# FPGA_Bypass_3V3.net
KiCad netlist of a schematic drawn in Altium Designer
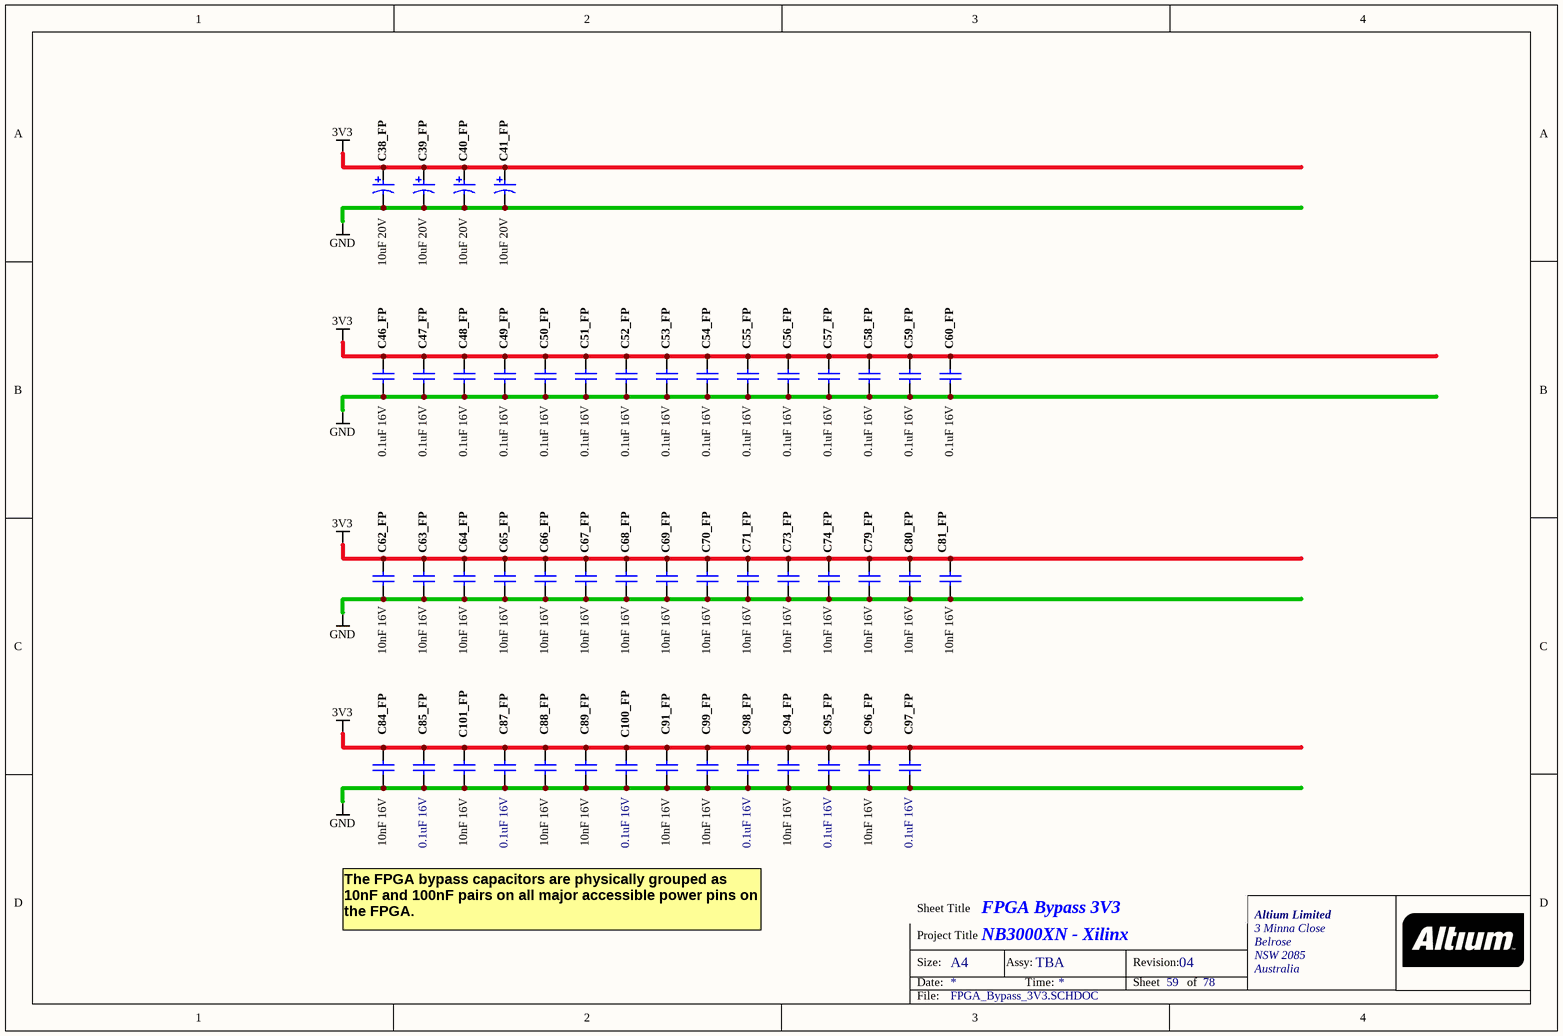
[diagram p0: FPGA_Bypass_3V3.SCHDOC]

(export (version "E")
  (design (tool "Eeschema 10.0.6"))
  (components
    (comp (ref "C38_FP")
      (value "10uF 20V")
      (footprint "CAPC3528-STAR")
      (description "Capacitor, Tantalum, 10uF 10% 20V MCCT-B (3528)")
      (fields (field (name "TOLERANCE") "10 %"))
      (libsource (lib "altium-import") (part "root_0_CAP-P_"))
    )
    (comp (ref "C39_FP")
      (value "10uF 20V")
      (footprint "CAPC3528-STAR")
      (description "Capacitor, Tantalum, 10uF 10% 20V MCCT-B (3528)")
      (fields (field (name "TOLERANCE") "10 %"))
      (libsource (lib "altium-import") (part "root_0_CAP-P_"))
    )
    (comp (ref "C40_FP")
      (value "10uF 20V")
      (footprint "CAPC3528-STAR")
      (description "Capacitor, Tantalum, 10uF 10% 20V MCCT-B (3528)")
      (fields (field (name "TOLERANCE") "10 %"))
      (libsource (lib "altium-import") (part "root_0_CAP-P_"))
    )
    (comp (ref "C41_FP")
      (value "10uF 20V")
      (footprint "CAPC3528-STAR")
      (description "Capacitor, Tantalum, 10uF 10% 20V MCCT-B (3528)")
      (fields (field (name "TOLERANCE") "10 %"))
      (libsource (lib "altium-import") (part "root_0_CAP-P_"))
    )
    (comp (ref "C46_FP")
      (value "0.1uF 16V")
      (footprint "CAPC1005-STAR")
      (description "Capacitor, Ceramic, 0.1uF 10% 16V 0402 (1005) X7R")
      (fields (field (name "TOLERANCE") "10 %"))
      (libsource (lib "altium-import") (part "root_0_mirrored_CAP-NP_"))
    )
    (comp (ref "C47_FP")
      (value "0.1uF 16V")
      (footprint "CAPC1005-STAR")
      (description "Capacitor, Ceramic, 0.1uF 10% 16V 0402 (1005) X7R")
      (fields (field (name "TOLERANCE") "10 %"))
      (libsource (lib "altium-import") (part "root_0_mirrored_CAP-NP_"))
    )
    (comp (ref "C48_FP")
      (value "0.1uF 16V")
      (footprint "CAPC1005-STAR")
      (description "Capacitor, Ceramic, 0.1uF 10% 16V 0402 (1005) X7R")
      (fields (field (name "TOLERANCE") "10 %"))
      (libsource (lib "altium-import") (part "root_0_mirrored_CAP-NP_"))
    )
    (comp (ref "C49_FP")
      (value "0.1uF 16V")
      (footprint "CAPC1005-STAR")
      (description "Capacitor, Ceramic, 0.1uF 10% 16V 0402 (1005) X7R")
      (fields (field (name "TOLERANCE") "10 %"))
      (libsource (lib "altium-import") (part "root_0_mirrored_CAP-NP_"))
    )
    (comp (ref "C50_FP")
      (value "0.1uF 16V")
      (footprint "CAPC1005-STAR")
      (description "Capacitor, Ceramic, 0.1uF 10% 16V 0402 (1005) X7R")
      (fields (field (name "TOLERANCE") "10 %"))
      (libsource (lib "altium-import") (part "root_0_mirrored_CAP-NP_"))
    )
    (comp (ref "C51_FP")
      (value "0.1uF 16V")
      (footprint "CAPC1005-STAR")
      (description "Capacitor, Ceramic, 0.1uF 10% 16V 0402 (1005) X7R")
      (fields (field (name "TOLERANCE") "10 %"))
      (libsource (lib "altium-import") (part "root_0_mirrored_CAP-NP_"))
    )
    (comp (ref "C52_FP")
      (value "0.1uF 16V")
      (footprint "CAPC1005-STAR")
      (description "Capacitor, Ceramic, 0.1uF 10% 16V 0402 (1005) X7R")
      (fields (field (name "TOLERANCE") "10 %"))
      (libsource (lib "altium-import") (part "root_0_mirrored_CAP-NP_"))
    )
    (comp (ref "C53_FP")
      (value "0.1uF 16V")
      (footprint "CAPC1005-STAR")
      (description "Capacitor, Ceramic, 0.1uF 10% 16V 0402 (1005) X7R")
      (fields (field (name "TOLERANCE") "10 %"))
      (libsource (lib "altium-import") (part "root_0_mirrored_CAP-NP_"))
    )
    (comp (ref "C54_FP")
      (value "0.1uF 16V")
      (footprint "CAPC1005-STAR")
      (description "Capacitor, Ceramic, 0.1uF 10% 16V 0402 (1005) X7R")
      (fields (field (name "TOLERANCE") "10 %"))
      (libsource (lib "altium-import") (part "root_0_mirrored_CAP-NP_"))
    )
    (comp (ref "C55_FP")
      (value "0.1uF 16V")
      (footprint "CAPC1005-STAR")
      (description "Capacitor, Ceramic, 0.1uF 10% 16V 0402 (1005) X7R")
      (fields (field (name "TOLERANCE") "10 %"))
      (libsource (lib "altium-import") (part "root_0_mirrored_CAP-NP_"))
    )
    (comp (ref "C56_FP")
      (value "0.1uF 16V")
      (footprint "CAPC1005-STAR")
      (description "Capacitor, Ceramic, 0.1uF 10% 16V 0402 (1005) X7R")
      (fields (field (name "TOLERANCE") "10 %"))
      (libsource (lib "altium-import") (part "root_0_mirrored_CAP-NP_"))
    )
    (comp (ref "C57_FP")
      (value "0.1uF 16V")
      (footprint "CAPC1005-STAR")
      (description "Capacitor, Ceramic, 0.1uF 10% 16V 0402 (1005) X7R")
      (fields (field (name "TOLERANCE") "10 %"))
      (libsource (lib "altium-import") (part "root_0_mirrored_CAP-NP_"))
    )
    (comp (ref "C58_FP")
      (value "0.1uF 16V")
      (footprint "CAPC1005-STAR")
      (description "Capacitor, Ceramic, 0.1uF 10% 16V 0402 (1005) X7R")
      (fields (field (name "TOLERANCE") "10 %"))
      (libsource (lib "altium-import") (part "root_0_mirrored_CAP-NP_"))
    )
    (comp (ref "C59_FP")
      (value "0.1uF 16V")
      (footprint "CAPC1005-STAR")
      (description "Capacitor, Ceramic, 0.1uF 10% 16V 0402 (1005) X7R")
      (fields (field (name "TOLERANCE") "10 %"))
      (libsource (lib "altium-import") (part "root_0_mirrored_CAP-NP_"))
    )
    (comp (ref "C60_FP")
      (value "0.1uF 16V")
      (footprint "CAPC1005-STAR")
      (description "Capacitor, Ceramic, 0.1uF 10% 16V 0402 (1005) X7R")
      (fields (field (name "TOLERANCE") "10 %"))
      (libsource (lib "altium-import") (part "root_0_mirrored_CAP-NP_"))
    )
    (comp (ref "C62_FP")
      (value "10nF 16V")
      (footprint "CAPC1005-STAR")
      (description "Capacitor, Ceramic, 10nF 10% 16V 0402 (1005) X7R")
      (fields (field (name "TOLERANCE") "10 %"))
      (libsource (lib "altium-import") (part "root_0_CAP-NP_"))
    )
    (comp (ref "C63_FP")
      (value "10nF 16V")
      (footprint "CAPC1005-STAR")
      (description "Capacitor, Ceramic, 10nF 10% 16V 0402 (1005) X7R")
      (fields (field (name "TOLERANCE") "10 %"))
      (libsource (lib "altium-import") (part "root_0_CAP-NP_"))
    )
    (comp (ref "C64_FP")
      (value "10nF 16V")
      (footprint "CAPC1005-STAR")
      (description "Capacitor, Ceramic, 10nF 10% 16V 0402 (1005) X7R")
      (fields (field (name "TOLERANCE") "10 %"))
      (libsource (lib "altium-import") (part "root_0_CAP-NP_"))
    )
    (comp (ref "C65_FP")
      (value "10nF 16V")
      (footprint "CAPC1005-STAR")
      (description "Capacitor, Ceramic, 10nF 10% 16V 0402 (1005) X7R")
      (fields (field (name "TOLERANCE") "10 %"))
      (libsource (lib "altium-import") (part "root_0_CAP-NP_"))
    )
    (comp (ref "C66_FP")
      (value "10nF 16V")
      (footprint "CAPC1005-STAR")
      (description "Capacitor, Ceramic, 10nF 10% 16V 0402 (1005) X7R")
      (fields (field (name "TOLERANCE") "10 %"))
      (libsource (lib "altium-import") (part "root_0_CAP-NP_"))
    )
    (comp (ref "C67_FP")
      (value "10nF 16V")
      (footprint "CAPC1005-STAR")
      (description "Capacitor, Ceramic, 10nF 10% 16V 0402 (1005) X7R")
      (fields (field (name "TOLERANCE") "10 %"))
      (libsource (lib "altium-import") (part "root_0_CAP-NP_"))
    )
    (comp (ref "C68_FP")
      (value "10nF 16V")
      (footprint "CAPC1005-STAR")
      (description "Capacitor, Ceramic, 10nF 10% 16V 0402 (1005) X7R")
      (fields (field (name "TOLERANCE") "10 %"))
      (libsource (lib "altium-import") (part "root_0_CAP-NP_"))
    )
    (comp (ref "C69_FP")
      (value "10nF 16V")
      (footprint "CAPC1005-STAR")
      (description "Capacitor, Ceramic, 10nF 10% 16V 0402 (1005) X7R")
      (fields (field (name "TOLERANCE") "10 %"))
      (libsource (lib "altium-import") (part "root_0_CAP-NP_"))
    )
    (comp (ref "C70_FP")
      (value "10nF 16V")
      (footprint "CAPC1005-STAR")
      (description "Capacitor, Ceramic, 10nF 10% 16V 0402 (1005) X7R")
      (fields (field (name "TOLERANCE") "10 %"))
      (libsource (lib "altium-import") (part "root_0_CAP-NP_"))
    )
    (comp (ref "C71_FP")
      (value "10nF 16V")
      (footprint "CAPC1005-STAR")
      (description "Capacitor, Ceramic, 10nF 10% 16V 0402 (1005) X7R")
      (fields (field (name "TOLERANCE") "10 %"))
      (libsource (lib "altium-import") (part "root_0_CAP-NP_"))
    )
    (comp (ref "C73_FP")
      (value "10nF 16V")
      (footprint "CAPC1005-STAR")
      (description "Capacitor, Ceramic, 10nF 10% 16V 0402 (1005) X7R")
      (fields (field (name "TOLERANCE") "10 %"))
      (libsource (lib "altium-import") (part "root_0_CAP-NP_"))
    )
    (comp (ref "C74_FP")
      (value "10nF 16V")
      (footprint "CAPC1005-STAR")
      (description "Capacitor, Ceramic, 10nF 10% 16V 0402 (1005) X7R")
      (fields (field (name "TOLERANCE") "10 %"))
      (libsource (lib "altium-import") (part "root_0_CAP-NP_"))
    )
    (comp (ref "C79_FP")
      (value "10nF 16V")
      (footprint "CAPC1005-STAR")
      (description "Capacitor, Ceramic, 10nF 10% 16V 0402 (1005) X7R")
      (fields (field (name "TOLERANCE") "10 %"))
      (libsource (lib "altium-import") (part "root_0_CAP-NP_"))
    )
    (comp (ref "C80_FP")
      (value "10nF 16V")
      (footprint "CAPC1005-STAR")
      (description "Capacitor, Ceramic, 10nF 10% 16V 0402 (1005) X7R")
      (fields (field (name "TOLERANCE") "10 %"))
      (libsource (lib "altium-import") (part "root_0_CAP-NP_"))
    )
    (comp (ref "C81_FP")
      (value "10nF 16V")
      (footprint "CAPC1005-STAR")
      (description "Capacitor, Ceramic, 10nF 10% 16V 0402 (1005) X7R")
      (fields (field (name "TOLERANCE") "10 %"))
      (libsource (lib "altium-import") (part "root_0_CAP-NP_"))
    )
    (comp (ref "C84_FP")
      (value "10nF 16V")
      (footprint "CAPC1005-STAR")
      (description "Capacitor, Ceramic, 10nF 10% 16V 0402 (1005) X7R")
      (fields (field (name "TOLERANCE") "10 %"))
      (libsource (lib "altium-import") (part "root_0_CAP-NP_"))
    )
    (comp (ref "C85_FP")
      (value "0.1uF 16V")
      (footprint "CAPC1005-STAR")
      (description "Capacitor, Ceramic, 0.1uF 10% 16V 0402 (1005) X7R")
      (fields (field (name "TOLERANCE") "10%"))
      (libsource (lib "AltiumDesignLibrary") (part "CAP-NP"))
    )
    (comp (ref "C87_FP")
      (value "0.1uF 16V")
      (footprint "CAPC1005-STAR")
      (description "Capacitor, Ceramic, 0.1uF 10% 16V 0402 (1005) X7R")
      (fields (field (name "TOLERANCE") "10%"))
      (libsource (lib "AltiumDesignLibrary") (part "CAP-NP"))
    )
    (comp (ref "C88_FP")
      (value "10nF 16V")
      (footprint "CAPC1005-STAR")
      (description "Capacitor, Ceramic, 10nF 10% 16V 0402 (1005) X7R")
      (fields (field (name "TOLERANCE") "10 %"))
      (libsource (lib "altium-import") (part "root_0_CAP-NP_"))
    )
    (comp (ref "C89_FP")
      (value "10nF 16V")
      (footprint "CAPC1005-STAR")
      (description "Capacitor, Ceramic, 10nF 10% 16V 0402 (1005) X7R")
      (fields (field (name "TOLERANCE") "10 %"))
      (libsource (lib "altium-import") (part "root_0_CAP-NP_"))
    )
    (comp (ref "C91_FP")
      (value "10nF 16V")
      (footprint "CAPC1005-STAR")
      (description "Capacitor, Ceramic, 10nF 10% 16V 0402 (1005) X7R")
      (fields (field (name "TOLERANCE") "10 %"))
      (libsource (lib "altium-import") (part "root_0_CAP-NP_"))
    )
    (comp (ref "C94_FP")
      (value "10nF 16V")
      (footprint "CAPC1005-STAR")
      (description "Capacitor, Ceramic, 10nF 10% 16V 0402 (1005) X7R")
      (fields (field (name "TOLERANCE") "10 %"))
      (libsource (lib "altium-import") (part "root_0_CAP-NP_"))
    )
    (comp (ref "C95_FP")
      (value "0.1uF 16V")
      (footprint "CAPC1005-STAR")
      (description "Capacitor, Ceramic, 0.1uF 10% 16V 0402 (1005) X7R")
      (fields (field (name "TOLERANCE") "10%"))
      (libsource (lib "AltiumDesignLibrary") (part "CAP-NP"))
    )
    (comp (ref "C96_FP")
      (value "10nF 16V")
      (footprint "CAPC1005-STAR")
      (description "Capacitor, Ceramic, 10nF 10% 16V 0402 (1005) X7R")
      (fields (field (name "TOLERANCE") "10 %"))
      (libsource (lib "altium-import") (part "root_0_CAP-NP_"))
    )
    (comp (ref "C97_FP")
      (value "0.1uF 16V")
      (footprint "CAPC1005-STAR")
      (description "Capacitor, Ceramic, 0.1uF 10% 16V 0402 (1005) X7R")
      (fields (field (name "TOLERANCE") "10%"))
      (libsource (lib "AltiumDesignLibrary") (part "CAP-NP"))
    )
    (comp (ref "C98_FP")
      (value "0.1uF 16V")
      (footprint "CAPC1005-STAR")
      (description "Capacitor, Ceramic, 0.1uF 10% 16V 0402 (1005) X7R")
      (fields (field (name "TOLERANCE") "10%"))
      (libsource (lib "AltiumDesignLibrary") (part "CAP-NP"))
    )
    (comp (ref "C99_FP")
      (value "10nF 16V")
      (footprint "CAPC1005-STAR")
      (description "Capacitor, Ceramic, 10nF 10% 16V 0402 (1005) X7R")
      (fields (field (name "TOLERANCE") "10 %"))
      (libsource (lib "altium-import") (part "root_0_CAP-NP_"))
    )
    (comp (ref "C100_FP")
      (value "0.1uF 16V")
      (footprint "CAPC1005-STAR")
      (description "Capacitor, Ceramic, 0.1uF 10% 16V 0402 (1005) X7R")
      (fields (field (name "TOLERANCE") "10%"))
      (libsource (lib "AltiumDesignLibrary") (part "CAP-NP"))
    )
    (comp (ref "C101_FP")
      (value "10nF 16V")
      (footprint "CAPC1005-STAR")
      (description "Capacitor, Ceramic, 10nF 10% 16V 0402 (1005) X7R")
      (fields (field (name "TOLERANCE") "10 %"))
      (libsource (lib "altium-import") (part "root_0_CAP-NP_"))
    )
  )
  (nets
    (net (code "1") (name "3V3") (class "Default")
      (node (ref "C100_FP") (pin "1") (pinfunction "1_1") (pintype "passive"))
      (node (ref "C101_FP") (pin "1") (pinfunction "1_1") (pintype "passive"))
      (node (ref "C38_FP") (pin "1") (pinfunction "1_1") (pintype "passive"))
      (node (ref "C39_FP") (pin "1") (pinfunction "1_1") (pintype "passive"))
      (node (ref "C40_FP") (pin "1") (pinfunction "1_1") (pintype "passive"))
      (node (ref "C41_FP") (pin "1") (pinfunction "1_1") (pintype "passive"))
      (node (ref "C46_FP") (pin "1") (pinfunction "1_1") (pintype "passive"))
      (node (ref "C47_FP") (pin "1") (pinfunction "1_1") (pintype "passive"))
      (node (ref "C48_FP") (pin "1") (pinfunction "1_1") (pintype "passive"))
      (node (ref "C49_FP") (pin "1") (pinfunction "1_1") (pintype "passive"))
      (node (ref "C50_FP") (pin "1") (pinfunction "1_1") (pintype "passive"))
      (node (ref "C51_FP") (pin "1") (pinfunction "1_1") (pintype "passive"))
      (node (ref "C52_FP") (pin "1") (pinfunction "1_1") (pintype "passive"))
      (node (ref "C53_FP") (pin "1") (pinfunction "1_1") (pintype "passive"))
      (node (ref "C54_FP") (pin "1") (pinfunction "1_1") (pintype "passive"))
      (node (ref "C55_FP") (pin "1") (pinfunction "1_1") (pintype "passive"))
      (node (ref "C56_FP") (pin "1") (pinfunction "1_1") (pintype "passive"))
      (node (ref "C57_FP") (pin "1") (pinfunction "1_1") (pintype "passive"))
      (node (ref "C58_FP") (pin "1") (pinfunction "1_1") (pintype "passive"))
      (node (ref "C59_FP") (pin "1") (pinfunction "1_1") (pintype "passive"))
      (node (ref "C60_FP") (pin "1") (pinfunction "1_1") (pintype "passive"))
      (node (ref "C62_FP") (pin "1") (pinfunction "1_1") (pintype "passive"))
      (node (ref "C63_FP") (pin "1") (pinfunction "1_1") (pintype "passive"))
      (node (ref "C64_FP") (pin "1") (pinfunction "1_1") (pintype "passive"))
      (node (ref "C65_FP") (pin "1") (pinfunction "1_1") (pintype "passive"))
      (node (ref "C66_FP") (pin "1") (pinfunction "1_1") (pintype "passive"))
      (node (ref "C67_FP") (pin "1") (pinfunction "1_1") (pintype "passive"))
      (node (ref "C68_FP") (pin "1") (pinfunction "1_1") (pintype "passive"))
      (node (ref "C69_FP") (pin "1") (pinfunction "1_1") (pintype "passive"))
      (node (ref "C70_FP") (pin "1") (pinfunction "1_1") (pintype "passive"))
      (node (ref "C71_FP") (pin "1") (pinfunction "1_1") (pintype "passive"))
      (node (ref "C73_FP") (pin "1") (pinfunction "1_1") (pintype "passive"))
      (node (ref "C74_FP") (pin "1") (pinfunction "1_1") (pintype "passive"))
      (node (ref "C79_FP") (pin "1") (pinfunction "1_1") (pintype "passive"))
      (node (ref "C80_FP") (pin "1") (pinfunction "1_1") (pintype "passive"))
      (node (ref "C81_FP") (pin "1") (pinfunction "1_1") (pintype "passive"))
      (node (ref "C84_FP") (pin "1") (pinfunction "1_1") (pintype "passive"))
      (node (ref "C85_FP") (pin "1") (pinfunction "1_1") (pintype "passive"))
      (node (ref "C87_FP") (pin "1") (pinfunction "1_1") (pintype "passive"))
      (node (ref "C88_FP") (pin "1") (pinfunction "1_1") (pintype "passive"))
      (node (ref "C89_FP") (pin "1") (pinfunction "1_1") (pintype "passive"))
      (node (ref "C91_FP") (pin "1") (pinfunction "1_1") (pintype "passive"))
      (node (ref "C94_FP") (pin "1") (pinfunction "1_1") (pintype "passive"))
      (node (ref "C95_FP") (pin "1") (pinfunction "1_1") (pintype "passive"))
      (node (ref "C96_FP") (pin "1") (pinfunction "1_1") (pintype "passive"))
      (node (ref "C97_FP") (pin "1") (pinfunction "1_1") (pintype "passive"))
      (node (ref "C98_FP") (pin "1") (pinfunction "1_1") (pintype "passive"))
      (node (ref "C99_FP") (pin "1") (pinfunction "1_1") (pintype "passive"))
    )
    (net (code "2") (name "GND") (class "Default")
      (node (ref "C100_FP") (pin "2") (pinfunction "2_2") (pintype "passive"))
      (node (ref "C101_FP") (pin "2") (pinfunction "2_2") (pintype "passive"))
      (node (ref "C38_FP") (pin "2") (pinfunction "2_2") (pintype "passive"))
      (node (ref "C39_FP") (pin "2") (pinfunction "2_2") (pintype "passive"))
      (node (ref "C40_FP") (pin "2") (pinfunction "2_2") (pintype "passive"))
      (node (ref "C41_FP") (pin "2") (pinfunction "2_2") (pintype "passive"))
      (node (ref "C46_FP") (pin "2") (pinfunction "2_2") (pintype "passive"))
      (node (ref "C47_FP") (pin "2") (pinfunction "2_2") (pintype "passive"))
      (node (ref "C48_FP") (pin "2") (pinfunction "2_2") (pintype "passive"))
      (node (ref "C49_FP") (pin "2") (pinfunction "2_2") (pintype "passive"))
      (node (ref "C50_FP") (pin "2") (pinfunction "2_2") (pintype "passive"))
      (node (ref "C51_FP") (pin "2") (pinfunction "2_2") (pintype "passive"))
      (node (ref "C52_FP") (pin "2") (pinfunction "2_2") (pintype "passive"))
      (node (ref "C53_FP") (pin "2") (pinfunction "2_2") (pintype "passive"))
      (node (ref "C54_FP") (pin "2") (pinfunction "2_2") (pintype "passive"))
      (node (ref "C55_FP") (pin "2") (pinfunction "2_2") (pintype "passive"))
      (node (ref "C56_FP") (pin "2") (pinfunction "2_2") (pintype "passive"))
      (node (ref "C57_FP") (pin "2") (pinfunction "2_2") (pintype "passive"))
      (node (ref "C58_FP") (pin "2") (pinfunction "2_2") (pintype "passive"))
      (node (ref "C59_FP") (pin "2") (pinfunction "2_2") (pintype "passive"))
      (node (ref "C60_FP") (pin "2") (pinfunction "2_2") (pintype "passive"))
      (node (ref "C62_FP") (pin "2") (pinfunction "2_2") (pintype "passive"))
      (node (ref "C63_FP") (pin "2") (pinfunction "2_2") (pintype "passive"))
      (node (ref "C64_FP") (pin "2") (pinfunction "2_2") (pintype "passive"))
      (node (ref "C65_FP") (pin "2") (pinfunction "2_2") (pintype "passive"))
      (node (ref "C66_FP") (pin "2") (pinfunction "2_2") (pintype "passive"))
      (node (ref "C67_FP") (pin "2") (pinfunction "2_2") (pintype "passive"))
      (node (ref "C68_FP") (pin "2") (pinfunction "2_2") (pintype "passive"))
      (node (ref "C69_FP") (pin "2") (pinfunction "2_2") (pintype "passive"))
      (node (ref "C70_FP") (pin "2") (pinfunction "2_2") (pintype "passive"))
      (node (ref "C71_FP") (pin "2") (pinfunction "2_2") (pintype "passive"))
      (node (ref "C73_FP") (pin "2") (pinfunction "2_2") (pintype "passive"))
      (node (ref "C74_FP") (pin "2") (pinfunction "2_2") (pintype "passive"))
      (node (ref "C79_FP") (pin "2") (pinfunction "2_2") (pintype "passive"))
      (node (ref "C80_FP") (pin "2") (pinfunction "2_2") (pintype "passive"))
      (node (ref "C81_FP") (pin "2") (pinfunction "2_2") (pintype "passive"))
      (node (ref "C84_FP") (pin "2") (pinfunction "2_2") (pintype "passive"))
      (node (ref "C85_FP") (pin "2") (pinfunction "2_2") (pintype "passive"))
      (node (ref "C87_FP") (pin "2") (pinfunction "2_2") (pintype "passive"))
      (node (ref "C88_FP") (pin "2") (pinfunction "2_2") (pintype "passive"))
      (node (ref "C89_FP") (pin "2") (pinfunction "2_2") (pintype "passive"))
      (node (ref "C91_FP") (pin "2") (pinfunction "2_2") (pintype "passive"))
      (node (ref "C94_FP") (pin "2") (pinfunction "2_2") (pintype "passive"))
      (node (ref "C95_FP") (pin "2") (pinfunction "2_2") (pintype "passive"))
      (node (ref "C96_FP") (pin "2") (pinfunction "2_2") (pintype "passive"))
      (node (ref "C97_FP") (pin "2") (pinfunction "2_2") (pintype "passive"))
      (node (ref "C98_FP") (pin "2") (pinfunction "2_2") (pintype "passive"))
      (node (ref "C99_FP") (pin "2") (pinfunction "2_2") (pintype "passive"))
    )
  )
)
